# power.net
KiCad netlist of a schematic drawn in Altium Designer
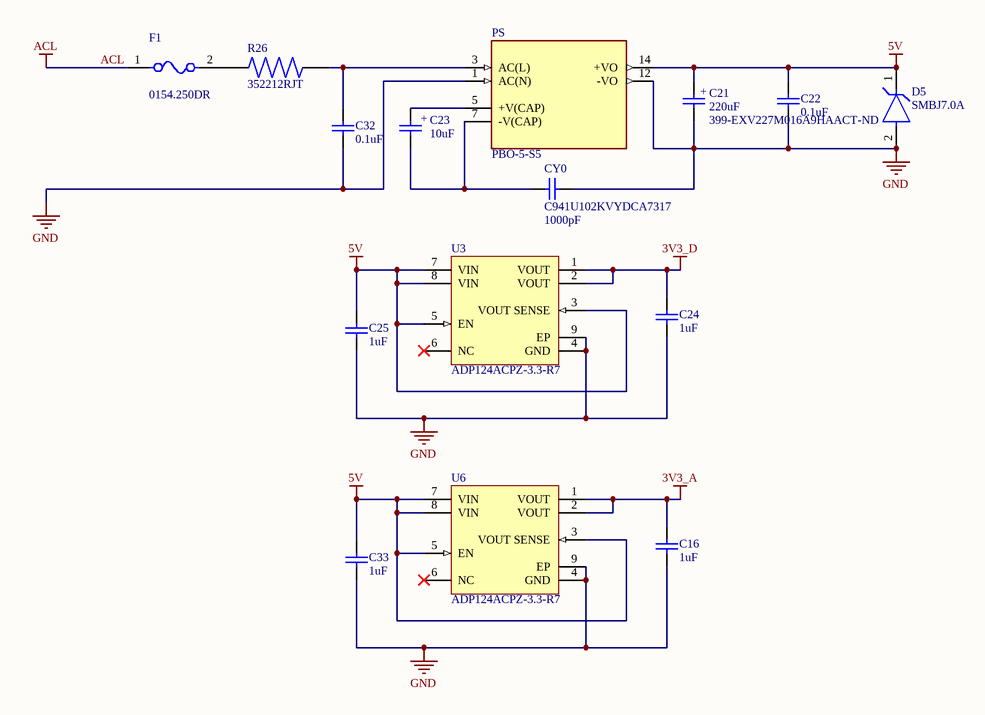
[diagram p0: power.SchDoc]

(export (version "E")
  (design (tool "Eeschema 10.0.6"))
  (components
    (comp (ref "C16")
      (value "1uF")
      (footprint "0603C")
      (fields
        (field (name "MANUFACTURER") "Kyocera AVX")
        (field (name "MANUFACTURER PART NUMBER") "0603YD105MAT2A")
        (field (name "TOLERANCE") "20%")
      )
      (libsource (lib "MB398B1") (part "0603YD105MAT2A"))
    )
    (comp (ref "C21")
      (value "220uF")
      (footprint "small_boi")
      (description "Aluminum electrolytic capacitor, 220uF, 16V")
      (fields
        (field (name "MANUFACTURER") "KEMET")
        (field (name "MANUFACTURER PART NUMBER") "C0603C103K3TACAUTO")
        (field (name "SUPPLIER PART NUMBER 1") "399-EXV227M016A9HAACT-ND")
      )
      (libsource (lib "MB398B1") (part "EXV227M016A9HAA"))
    )
    (comp (ref "C22")
      (value "0.1uF")
      (footprint "0603C")
      (description "Cap Ceramic 0.1uF 25V X7R 10% Pad SMD 0603 125C Automotive T/R")
      (fields
        (field (name "MANUFACTURER") "Kyocera AVX")
        (field (name "MANUFACTURER PART NUMBER") "06033C104K4T4A")
      )
      (libsource (lib "MB398B1") (part "06033C104K4T4A"))
    )
    (comp (ref "C23")
      (value "10uF")
      (footprint "PCBComponent_1")
      (description "Aluminum Electrolitic Capacitor, 10uF, 450Vac")
      (fields
        (field (name "MANUFACTURER") "KEMET")
        (field (name "MANUFACTURER PART NUMBER") "C0603C103K3TACAUTO")
      )
      (libsource (lib "MB398B1") (part "MAL215299704E3"))
    )
    (comp (ref "C24")
      (value "1uF")
      (footprint "0603C")
      (fields
        (field (name "MANUFACTURER") "Kyocera AVX")
        (field (name "MANUFACTURER PART NUMBER") "0603YD105MAT2A")
        (field (name "TOLERANCE") "20%")
      )
      (libsource (lib "MB398B1") (part "0603YD105MAT2A"))
    )
    (comp (ref "C25")
      (value "1uF")
      (footprint "0603C")
      (fields
        (field (name "MANUFACTURER") "Kyocera AVX")
        (field (name "MANUFACTURER PART NUMBER") "0603YD105MAT2A")
        (field (name "TOLERANCE") "20%")
      )
      (libsource (lib "MB398B1") (part "0603YD105MAT2A"))
    )
    (comp (ref "C32")
      (value "0.1uF")
      (footprint "1.083FILM")
      (description "Capacitor")
      (fields
        (field (name "MANUFACTURER") "KEMET")
        (field (name "MANUFACTURER PART NUMBER") "C0603C103K3TACAUTO")
      )
      (libsource (lib "MB398B1") (part "104MKP275KC"))
    )
    (comp (ref "C33")
      (value "1uF")
      (footprint "0603C")
      (fields
        (field (name "MANUFACTURER") "Kyocera AVX")
        (field (name "MANUFACTURER PART NUMBER") "0603YD105MAT2A")
        (field (name "TOLERANCE") "20%")
      )
      (libsource (lib "MB398B1") (part "0603YD105MAT2A"))
    )
    (comp (ref "CY0")
      (value "C941U102KVYDCA7317")
      (footprint "MURA-DE1E3KX222MA5")
      (description "Ceramic Capacitor, 2.2 nF, +/- 20%, 250 V, -25 to 85 degC, 2-Pin THD, RoHS, Bulk")
      (fields (field (name "MANUFACTURER") "Murata") (field (name "CAPACITANCE") "1000pF"))
      (libsource (lib "Altium Content Vault") (part "CAP-NP-2"))
    )
    (comp (ref "D5")
      (value "SMBJ7.0A")
      (footprint "FP-SMBJ-MFG")
      (description "TVS DIODE 5V 9.2V DO214AA")
      (fields
        (field (name "OCTOPART") "https://octopart.com/smbj5.0a-littelfuse-8835")
        (field (name "MANUFACTURER") "Littelfuse Inc")
      )
      (libsource (lib "Altium Content Vault") (part "f813f71cba58e380607f5dd3caf9714"))
    )
    (comp (ref "F1")
      (value "0154.250DR")
      (footprint "FP-0154-MFG")
      (description "FUSE BOARD MNT 250MA 125VAC/VDC")
      (fields
        (field (name "MANUFACTURER") "Littelfuse")
        (field (name "OCTOPART") "https://octopart.com/0154.250dr-littelfuse-565851")
      )
      (libsource (lib "Altium Content Vault") (part "5bcf9b9f640e542cf0359d10258e979"))
    )
    (comp (ref "PS")
      (value "PBO-5-S5")
      (footprint "CONV_PBO-5-S5")
      (description "5 W, Single Output, Open Frame, Board Mount, Ac-Dc Power Supply")
      (fields (field (name "MF") "CUI Inc."))
      (libsource (lib "PBO-5-S5") (part "PBO-5-S5"))
    )
    (comp (ref "R26")
      (value "352212RJT")
      (footprint "RESC6332X120N")
      (description "Thick Film Resistors - SMD 3522 12R 5% 3W")
      (fields (field (name "MF") "TE Connectivity") (field (name "TOLERANCE") "5%"))
      (libsource (lib "352212RJT") (part "352212RJT"))
    )
    (comp (ref "U3")
      (value "ADP124ACPZ-3.3-R7")
      (footprint "ADI-CP-8-8_V")
      (fields (field (name "MANUFACTURER") "Analog Devices"))
      (libsource (lib "Altium Content Vault") (part "ADI-ADP124-CP-8-8"))
    )
    (comp (ref "U6")
      (value "ADP124ACPZ-3.3-R7")
      (footprint "ADI-CP-8-8_V")
      (fields (field (name "MANUFACTURER") "Analog Devices"))
      (libsource (lib "Altium Content Vault") (part "ADI-ADP124-CP-8-8"))
    )
  )
  (nets
    (net (code "1") (name "3V3_A") (class "Default")
      (node (ref "C16") (pin "2") (pinfunction "2_2") (pintype "passive"))
      (node (ref "U6") (pin "1") (pinfunction "VOUT_1") (pintype "power_in"))
      (node (ref "U6") (pin "2") (pinfunction "VOUT_2") (pintype "power_in"))
    )
    (net (code "2") (name "3V3_D") (class "Default")
      (node (ref "C24") (pin "2") (pinfunction "2_2") (pintype "passive"))
      (node (ref "U3") (pin "1") (pinfunction "VOUT_1") (pintype "power_in"))
      (node (ref "U3") (pin "2") (pinfunction "VOUT_2") (pintype "power_in"))
    )
    (net (code "3") (name "5V") (class "Default")
      (node (ref "C21") (pin "1") (pinfunction "1_1") (pintype "passive"))
      (node (ref "C22") (pin "2") (pinfunction "2_2") (pintype "passive"))
      (node (ref "C25") (pin "2") (pinfunction "2_2") (pintype "passive"))
      (node (ref "C33") (pin "2") (pinfunction "2_2") (pintype "passive"))
      (node (ref "D5") (pin "1") (pinfunction "C_1") (pintype "passive"))
      (node (ref "PS") (pin "14") (pinfunction "+VO_14") (pintype "output"))
      (node (ref "U3") (pin "3") (pinfunction "VOUT_SENSE_3") (pintype "input"))
      (node (ref "U3") (pin "5") (pinfunction "EN_5") (pintype "input"))
      (node (ref "U3") (pin "7") (pinfunction "VIN_7") (pintype "power_in"))
      (node (ref "U3") (pin "8") (pinfunction "VIN_8") (pintype "power_in"))
      (node (ref "U6") (pin "3") (pinfunction "VOUT_SENSE_3") (pintype "input"))
      (node (ref "U6") (pin "5") (pinfunction "EN_5") (pintype "input"))
      (node (ref "U6") (pin "7") (pinfunction "VIN_7") (pintype "power_in"))
      (node (ref "U6") (pin "8") (pinfunction "VIN_8") (pintype "power_in"))
    )
    (net (code "4") (name "ACL") (class "Default")
      (node (ref "F1") (pin "1") (pinfunction "1_1") (pintype "passive"))
    )
    (net (code "5") (name "GND") (class "Default")
      (node (ref "C16") (pin "1") (pinfunction "1_1") (pintype "passive"))
      (node (ref "C21") (pin "2") (pinfunction "2_2") (pintype "passive"))
      (node (ref "C22") (pin "1") (pinfunction "1_1") (pintype "passive"))
      (node (ref "C24") (pin "1") (pinfunction "1_1") (pintype "passive"))
      (node (ref "C25") (pin "1") (pinfunction "1_1") (pintype "passive"))
      (node (ref "C32") (pin "1") (pinfunction "1_1") (pintype "passive"))
      (node (ref "C33") (pin "1") (pinfunction "1_1") (pintype "passive"))
      (node (ref "CY0") (pin "2") (pinfunction "2_2") (pintype "passive"))
      (node (ref "D5") (pin "2") (pinfunction "A_2") (pintype "passive"))
      (node (ref "PS") (pin "1") (pinfunction "AC(N)_1") (pintype "input"))
      (node (ref "PS") (pin "12") (pinfunction "-VO_12") (pintype "output"))
      (node (ref "U3") (pin "4") (pinfunction "GND_4") (pintype "power_in"))
      (node (ref "U3") (pin "9") (pinfunction "EP_9") (pintype "power_in"))
      (node (ref "U6") (pin "4") (pinfunction "GND_4") (pintype "power_in"))
      (node (ref "U6") (pin "9") (pinfunction "EP_9") (pintype "power_in"))
    )
    (net (code "6") (name "Net-(F1-Pad2)") (class "Default")
      (node (ref "F1") (pin "2") (pinfunction "2_2") (pintype "passive"))
      (node (ref "R26") (pin "1") (pinfunction "1_1") (pintype "passive"))
    )
    (net (code "7") (name "Net-(PS-+V(CAP))") (class "Default")
      (node (ref "C23") (pin "1") (pinfunction "1_1") (pintype "passive"))
      (node (ref "PS") (pin "5") (pinfunction "+V(CAP)_5") (pintype "passive"))
    )
    (net (code "8") (name "Net-(PS--V(CAP))") (class "Default")
      (node (ref "C23") (pin "2") (pinfunction "2_2") (pintype "passive"))
      (node (ref "CY0") (pin "1") (pinfunction "1_1") (pintype "passive"))
      (node (ref "PS") (pin "7") (pinfunction "-V(CAP)_7") (pintype "passive"))
    )
    (net (code "9") (name "Net-(PS-AC(L))") (class "Default")
      (node (ref "C32") (pin "2") (pinfunction "2_2") (pintype "passive"))
      (node (ref "PS") (pin "3") (pinfunction "AC(L)_3") (pintype "input"))
      (node (ref "R26") (pin "2") (pinfunction "2_2") (pintype "passive"))
    )
    (net (code "10") (name "unconnected-(U3-NC-Pad6)") (class "Default")
      (node (ref "U3") (pin "6") (pinfunction "NC_6") (pintype "passive+no_connect"))
    )
    (net (code "11") (name "unconnected-(U6-NC-Pad6)") (class "Default")
      (node (ref "U6") (pin "6") (pinfunction "NC_6") (pintype "passive+no_connect"))
    )
  )
)
